# GPI_IF.net
KiCad netlist of a schematic drawn in Altium Designer
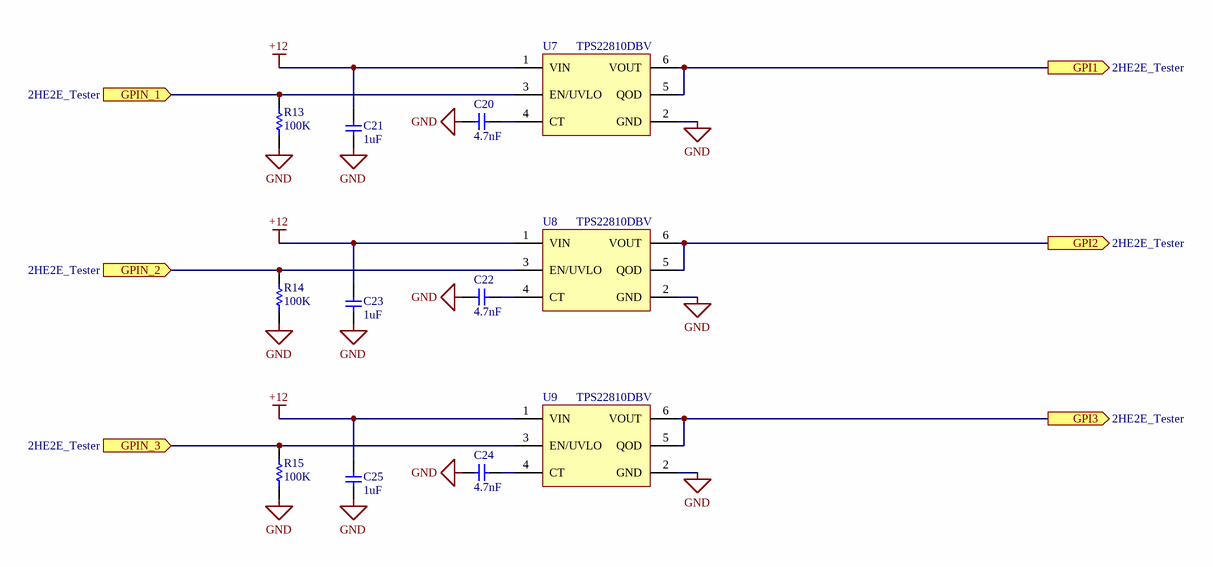
[diagram p0: GPI_IF.SchDoc]

(export (version "E")
  (design (tool "Eeschema 10.0.6"))
  (components
    (comp (ref "C20")
      (value "4.7nF")
      (footprint "0603M-C")
      (description "Ceramic Capacitor")
      (fields (field (name "Comment") "Cap Ceramic"))
      (libsource (lib "Plume") (part "Cap Ceramic"))
    )
    (comp (ref "C21")
      (value "1uF")
      (footprint "0603M-C")
      (description "Ceramic Capacitor 16V")
      (fields (field (name "Comment") "Cap Ceramic"))
      (libsource (lib "Plume") (part "Cap Ceramic"))
    )
    (comp (ref "C22")
      (value "4.7nF")
      (footprint "0603M-C")
      (description "Ceramic Capacitor")
      (fields (field (name "Comment") "Cap Ceramic"))
      (libsource (lib "Plume") (part "Cap Ceramic"))
    )
    (comp (ref "C23")
      (value "1uF")
      (footprint "0603M-C")
      (description "Ceramic Capacitor 16V")
      (fields (field (name "Comment") "Cap Ceramic"))
      (libsource (lib "Plume") (part "Cap Ceramic"))
    )
    (comp (ref "C24")
      (value "4.7nF")
      (footprint "0603M-C")
      (description "Ceramic Capacitor")
      (fields (field (name "Comment") "Cap Ceramic"))
      (libsource (lib "Plume") (part "Cap Ceramic"))
    )
    (comp (ref "C25")
      (value "1uF")
      (footprint "0603M-C")
      (description "Ceramic Capacitor 16V")
      (fields (field (name "Comment") "Cap Ceramic"))
      (libsource (lib "Plume") (part "Cap Ceramic"))
    )
    (comp (ref "R13")
      (value "100K")
      (footprint "0603M")
      (description "Resistor")
      (libsource (lib "Plume") (part "Resistor"))
    )
    (comp (ref "R14")
      (value "100K")
      (footprint "0603M")
      (description "Resistor")
      (libsource (lib "Plume") (part "Resistor"))
    )
    (comp (ref "R15")
      (value "100K")
      (footprint "0603M")
      (description "Resistor")
      (libsource (lib "Plume") (part "Resistor"))
    )
    (comp (ref "U7")
      (value "TPS22810DBV")
      (footprint "SOT23-6 (SOT26)")
      (description "Load Switch With Thermal Protection 2.7-18-V, 79-mΩ On-Resistance")
      (libsource (lib "Plume") (part "TPS22810DBV"))
    )
    (comp (ref "U8")
      (value "TPS22810DBV")
      (footprint "SOT23-6 (SOT26)")
      (description "Load Switch With Thermal Protection 2.7-18-V, 79-mΩ On-Resistance")
      (libsource (lib "Plume") (part "TPS22810DBV"))
    )
    (comp (ref "U9")
      (value "TPS22810DBV")
      (footprint "SOT23-6 (SOT26)")
      (description "Load Switch With Thermal Protection 2.7-18-V, 79-mΩ On-Resistance")
      (libsource (lib "Plume") (part "TPS22810DBV"))
    )
  )
  (nets
    (net (code "1") (name "+12") (class "Default")
      (node (ref "C21") (pin "1") (pinfunction "1_1") (pintype "passive"))
      (node (ref "C23") (pin "1") (pinfunction "1_1") (pintype "passive"))
      (node (ref "C25") (pin "1") (pinfunction "1_1") (pintype "passive"))
      (node (ref "U7") (pin "1") (pinfunction "VIN_1") (pintype "passive"))
      (node (ref "U8") (pin "1") (pinfunction "VIN_1") (pintype "passive"))
      (node (ref "U9") (pin "1") (pinfunction "VIN_1") (pintype "passive"))
    )
    (net (code "2") (name "/GPI1") (class "Default")
      (node (ref "U7") (pin "5") (pinfunction "QOD_5") (pintype "passive"))
      (node (ref "U7") (pin "6") (pinfunction "VOUT_6") (pintype "passive"))
    )
    (net (code "3") (name "/GPI2") (class "Default")
      (node (ref "U8") (pin "5") (pinfunction "QOD_5") (pintype "passive"))
      (node (ref "U8") (pin "6") (pinfunction "VOUT_6") (pintype "passive"))
    )
    (net (code "4") (name "/GPI3") (class "Default")
      (node (ref "U9") (pin "5") (pinfunction "QOD_5") (pintype "passive"))
      (node (ref "U9") (pin "6") (pinfunction "VOUT_6") (pintype "passive"))
    )
    (net (code "5") (name "/GPIN_1") (class "Default")
      (node (ref "R13") (pin "2") (pinfunction "2_2") (pintype "passive"))
      (node (ref "U7") (pin "3") (pinfunction "EN/UVLO_3") (pintype "passive"))
    )
    (net (code "6") (name "/GPIN_2") (class "Default")
      (node (ref "R14") (pin "2") (pinfunction "2_2") (pintype "passive"))
      (node (ref "U8") (pin "3") (pinfunction "EN/UVLO_3") (pintype "passive"))
    )
    (net (code "7") (name "/GPIN_3") (class "Default")
      (node (ref "R15") (pin "2") (pinfunction "2_2") (pintype "passive"))
      (node (ref "U9") (pin "3") (pinfunction "EN/UVLO_3") (pintype "passive"))
    )
    (net (code "8") (name "GND") (class "Default")
      (node (ref "C20") (pin "2") (pinfunction "2_2") (pintype "passive"))
      (node (ref "C21") (pin "2") (pinfunction "2_2") (pintype "passive"))
      (node (ref "C22") (pin "2") (pinfunction "2_2") (pintype "passive"))
      (node (ref "C23") (pin "2") (pinfunction "2_2") (pintype "passive"))
      (node (ref "C24") (pin "2") (pinfunction "2_2") (pintype "passive"))
      (node (ref "C25") (pin "2") (pinfunction "2_2") (pintype "passive"))
      (node (ref "R13") (pin "1") (pinfunction "1_1") (pintype "passive"))
      (node (ref "R14") (pin "1") (pinfunction "1_1") (pintype "passive"))
      (node (ref "R15") (pin "1") (pinfunction "1_1") (pintype "passive"))
      (node (ref "U7") (pin "2") (pinfunction "GND_2") (pintype "passive"))
      (node (ref "U8") (pin "2") (pinfunction "GND_2") (pintype "passive"))
      (node (ref "U9") (pin "2") (pinfunction "GND_2") (pintype "passive"))
    )
    (net (code "9") (name "Net-(U7-CT)") (class "Default")
      (node (ref "C20") (pin "1") (pinfunction "1_1") (pintype "passive"))
      (node (ref "U7") (pin "4") (pinfunction "CT_4") (pintype "passive"))
    )
    (net (code "10") (name "Net-(U8-CT)") (class "Default")
      (node (ref "C22") (pin "1") (pinfunction "1_1") (pintype "passive"))
      (node (ref "U8") (pin "4") (pinfunction "CT_4") (pintype "passive"))
    )
    (net (code "11") (name "Net-(U9-CT)") (class "Default")
      (node (ref "C24") (pin "1") (pinfunction "1_1") (pintype "passive"))
      (node (ref "U9") (pin "4") (pinfunction "CT_4") (pintype "passive"))
    )
  )
)
